# touch_control_pickit_adapter.net
KiCad netlist of a schematic drawn in Altium Designer
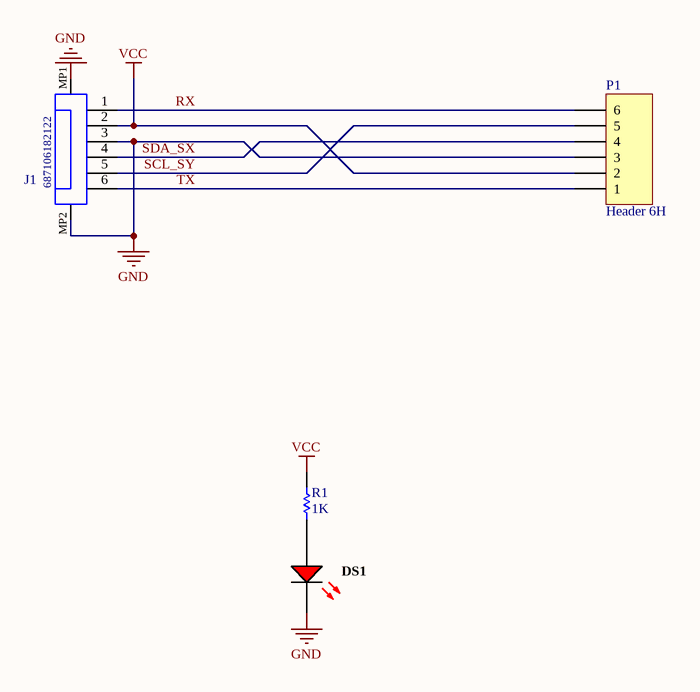
[diagram p0: touch_control_pickit_adapter.SchDoc]

(export (version "E")
  (design (tool "Eeschema 10.0.6"))
  (components
    (comp (ref "DS1")
      (value "APG1608SURKC/T")
      (footprint "KING-LED0603-25-RED_V")
      (fields (field (name "MANUFACTURER") "Kingbright"))
      (libsource (lib "Altium Content Vault") (part "KING-LED_RED_A1K2-2"))
    )
    (comp (ref "J1")
      (value "687106182122")
      (footprint "687106182122")
      (description "SMT ZIF Connectors WR-FPC, Horizontal, Back Locking Dual Contact, pitch 0.5 mm, 6 pins")
      (fields (field (name "MANUFACTURER") "Wurth Elektronik") (field (name "PUBLISHER") "WurthElektronik"))
      (libsource (lib "Altium Content Vault") (part "WE-68X1061XXX22-6"))
    )
    (comp (ref "P1")
      (value "Header 6H")
      (footprint "HDR1X6H")
      (description "Header, 6-Pin, Right Angle")
      (fields (field (name "PUBLISHER") "Altium Limited"))
      (libsource (lib "Miscellaneous Connectors") (part "Header 6H"))
    )
    (comp (ref "R1")
      (value "1K")
      (footprint "RESC0603(1608)_N")
      (description "10K 0.1W 1% 0603 (1608 Metric)  SMD")
      (fields (field (name "POWER") "0.1 W") (field (name "TOLERANCE") "1 %"))
      (libsource (lib "Altium Content Vault") (part "RES"))
    )
  )
  (nets
    (net (code "1") (name "/RX") (class "Default")
      (node (ref "J1") (pin "1") (pinfunction "1_1") (pintype "passive"))
      (node (ref "P1") (pin "6") (pinfunction "6_6") (pintype "passive"))
    )
    (net (code "2") (name "/SCL_SY") (class "Default")
      (node (ref "J1") (pin "5") (pinfunction "5_5") (pintype "passive"))
      (node (ref "P1") (pin "5") (pinfunction "5_5") (pintype "passive"))
    )
    (net (code "3") (name "/SDA_SX") (class "Default")
      (node (ref "J1") (pin "4") (pinfunction "4_4") (pintype "passive"))
      (node (ref "P1") (pin "4") (pinfunction "4_4") (pintype "passive"))
    )
    (net (code "4") (name "/TX") (class "Default")
      (node (ref "J1") (pin "6") (pinfunction "6_6") (pintype "passive"))
      (node (ref "P1") (pin "1") (pinfunction "1_1") (pintype "passive"))
    )
    (net (code "5") (name "GND") (class "Default")
      (node (ref "DS1") (pin "2") (pinfunction "K_2") (pintype "passive"))
      (node (ref "J1") (pin "3") (pinfunction "3_3") (pintype "passive"))
      (node (ref "J1") (pin "MP1") (pinfunction "MP1_MP1") (pintype "passive"))
      (node (ref "J1") (pin "MP2") (pinfunction "MP2_MP2") (pintype "passive"))
      (node (ref "P1") (pin "3") (pinfunction "3_3") (pintype "passive"))
    )
    (net (code "6") (name "Net-(DS1-A)") (class "Default")
      (node (ref "DS1") (pin "1") (pinfunction "A_1") (pintype "passive"))
      (node (ref "R1") (pin "2") (pinfunction "2_2") (pintype "passive"))
    )
    (net (code "7") (name "VCC") (class "Default")
      (node (ref "J1") (pin "2") (pinfunction "2_2") (pintype "passive"))
      (node (ref "P1") (pin "2") (pinfunction "2_2") (pintype "passive"))
      (node (ref "R1") (pin "1") (pinfunction "1_1") (pintype "passive"))
    )
  )
)
